# PCB_Punto_de_CobroV2.net
KiCad netlist of a schematic drawn in EAGLE
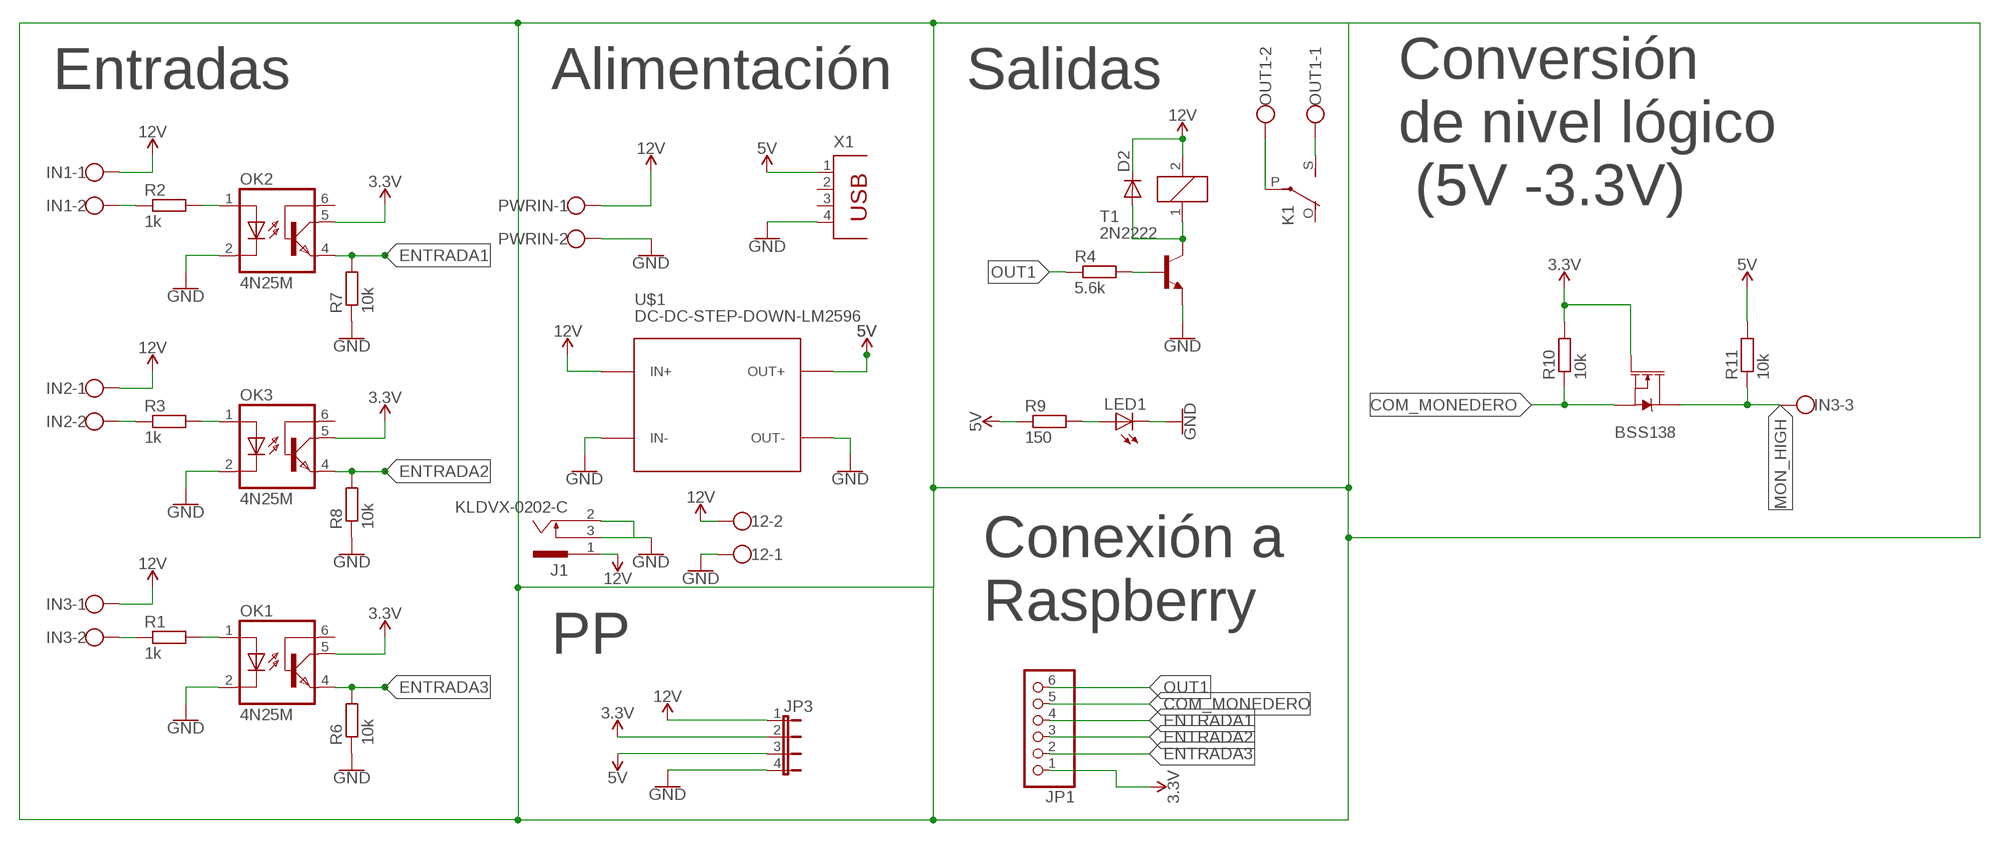
[diagram p0: schematic, sheet 1]

(export (version "E")
  (design (tool "Eeschema 10.0.6"))
  (components
    (comp (ref "12")
      (value "W237-102")
      (footprint "eagle-import:W237-102")
      (fields (field (name "MPN") "237-102"))
      (libsource (lib "eagle-import") (part "W237-102"))
    )
    (comp (ref "D2")
      (value "1N4148DO35-7")
      (footprint "eagle-import:DO35-7")
      (libsource (lib "eagle-import") (part "1N4148DO35-7"))
    )
    (comp (ref "IN1")
      (value "W237-102")
      (footprint "eagle-import:W237-102")
      (fields (field (name "MPN") "237-102"))
      (libsource (lib "eagle-import") (part "W237-102"))
    )
    (comp (ref "IN2")
      (value "W237-102")
      (footprint "eagle-import:W237-102")
      (fields (field (name "MPN") "237-102"))
      (libsource (lib "eagle-import") (part "W237-102"))
    )
    (comp (ref "IN3")
      (value "W237-103")
      (footprint "eagle-import:W237-103")
      (fields (field (name "MPN") "237-103"))
      (libsource (lib "eagle-import") (part "W237-103"))
    )
    (comp (ref "J1")
      (value "KLDVX-0202-C")
      (footprint "eagle-import:KLDVX-0202-C")
      (libsource (lib "eagle-import") (part "KLDVX-0202-C"))
    )
    (comp (ref "JP1")
      (value "PINHD-1X6")
      (footprint "eagle-import:1X06")
      (libsource (lib "eagle-import") (part "PINHD-1X6"))
    )
    (comp (ref "JP3")
      (value "JP4E")
      (footprint "eagle-import:JP4")
      (libsource (lib "eagle-import") (part "JP4E"))
    )
    (comp (ref "K1")
      (value "G5L")
      (footprint "eagle-import:G5LE")
      (libsource (lib "eagle-import") (part "G5L"))
    )
    (comp (ref "LED1")
      (value "LED5MM")
      (footprint "eagle-import:LED5MM")
      (libsource (lib "eagle-import") (part "LED5MM"))
    )
    (comp (ref "OK1")
      (value "4N25M")
      (footprint "eagle-import:DIL06")
      (fields (field (name "MPN") "4N25-M"))
      (libsource (lib "eagle-import") (part "4N?M25"))
    )
    (comp (ref "OK2")
      (value "4N25M")
      (footprint "eagle-import:DIL06")
      (fields (field (name "MPN") "4N25-M"))
      (libsource (lib "eagle-import") (part "4N?M25"))
    )
    (comp (ref "OK3")
      (value "4N25M")
      (footprint "eagle-import:DIL06")
      (fields (field (name "MPN") "4N25-M"))
      (libsource (lib "eagle-import") (part "4N?M25"))
    )
    (comp (ref "OUT1")
      (value "W237-102")
      (footprint "eagle-import:W237-102")
      (fields (field (name "MPN") "237-102"))
      (libsource (lib "eagle-import") (part "W237-102"))
    )
    (comp (ref "PWRIN")
      (value "W237-102")
      (footprint "eagle-import:W237-102")
      (fields (field (name "MPN") "237-102"))
      (libsource (lib "eagle-import") (part "W237-102"))
    )
    (comp (ref "Q3")
      (value "BSS138")
      (footprint "eagle-import:SOT23-3")
      (libsource (lib "eagle-import") (part "MOSFET-NCH-BSS138"))
    )
    (comp (ref "R1")
      (value "1k")
      (footprint "eagle-import:0204_7")
      (libsource (lib "eagle-import") (part "R0204/7"))
    )
    (comp (ref "R2")
      (value "1k")
      (footprint "eagle-import:0204_7")
      (libsource (lib "eagle-import") (part "R0204/7"))
    )
    (comp (ref "R3")
      (value "1k")
      (footprint "eagle-import:0204_7")
      (libsource (lib "eagle-import") (part "R0204/7"))
    )
    (comp (ref "R4")
      (value "5.6k")
      (footprint "eagle-import:0204_7")
      (libsource (lib "eagle-import") (part "R0204/7"))
    )
    (comp (ref "R6")
      (value "10k")
      (footprint "eagle-import:0204_7")
      (libsource (lib "eagle-import") (part "R0204/7"))
    )
    (comp (ref "R7")
      (value "10k")
      (footprint "eagle-import:0204_7")
      (libsource (lib "eagle-import") (part "R0204/7"))
    )
    (comp (ref "R8")
      (value "10k")
      (footprint "eagle-import:0204_7")
      (libsource (lib "eagle-import") (part "R0204/7"))
    )
    (comp (ref "R9")
      (value "150")
      (footprint "eagle-import:0204_7")
      (libsource (lib "eagle-import") (part "R0204/7"))
    )
    (comp (ref "R10")
      (value "10k")
      (footprint "eagle-import:0204_7")
      (libsource (lib "eagle-import") (part "R0204/7"))
    )
    (comp (ref "R11")
      (value "10k")
      (footprint "eagle-import:0204_7")
      (libsource (lib "eagle-import") (part "R0204/7"))
    )
    (comp (ref "T1")
      (value "2N2222")
      (footprint "eagle-import:TO18")
      (libsource (lib "eagle-import") (part "2N2222"))
    )
    (comp (ref "U$1")
      (value "DC-DC-STEP-DOWN-LM2596")
      (footprint "eagle-import:DC-DC-STEP-DOWN-LM2596")
      (libsource (lib "eagle-import") (part "DC-DC-STEP-DOWN-LM2596"))
    )
    (comp (ref "X1")
      (value "PN87520")
      (footprint "eagle-import:PN87520")
      (libsource (lib "eagle-import") (part "PN87520"))
    )
  )
  (nets
    (net (code "1") (name "3.3V") (class "Default")
      (node (ref "JP1") (pin "1") (pinfunction "1_1") (pintype "passive"))
      (node (ref "JP3") (pin "2") (pinfunction "2_2") (pintype "passive"))
      (node (ref "OK1") (pin "5") (pinfunction "COL_5") (pintype "passive"))
      (node (ref "OK2") (pin "5") (pinfunction "COL_5") (pintype "passive"))
      (node (ref "OK3") (pin "5") (pinfunction "COL_5") (pintype "passive"))
      (node (ref "Q3") (pin "1") (pinfunction "G_1") (pintype "bidirectional"))
      (node (ref "R10") (pin "2") (pinfunction "2_2") (pintype "passive"))
    )
    (net (code "2") (name "5V") (class "Default")
      (node (ref "JP3") (pin "3") (pinfunction "3_3") (pintype "passive"))
      (node (ref "R11") (pin "2") (pinfunction "2_2") (pintype "passive"))
      (node (ref "R9") (pin "1") (pinfunction "1_1") (pintype "passive"))
      (node (ref "U$1") (pin "OUT+") (pinfunction "OUT+_OUT+") (pintype "bidirectional"))
      (node (ref "X1") (pin "1") (pinfunction "1_1") (pintype "passive"))
    )
    (net (code "3") (name "12V") (class "Default")
      (node (ref "12") (pin "2") (pinfunction "KL_2") (pintype "passive"))
      (node (ref "D2") (pin "C") (pinfunction "C_C") (pintype "passive"))
      (node (ref "IN1") (pin "1") (pinfunction "KL_1") (pintype "passive"))
      (node (ref "IN2") (pin "1") (pinfunction "KL_1") (pintype "passive"))
      (node (ref "IN3") (pin "1") (pinfunction "KL_1") (pintype "passive"))
      (node (ref "J1") (pin "1") (pinfunction "1_1") (pintype "passive"))
      (node (ref "JP3") (pin "1") (pinfunction "1_1") (pintype "passive"))
      (node (ref "K1") (pin "2") (pinfunction "2_2") (pintype "passive"))
      (node (ref "PWRIN") (pin "1") (pinfunction "KL_1") (pintype "passive"))
      (node (ref "U$1") (pin "IN+") (pinfunction "IN+_IN+") (pintype "bidirectional"))
    )
    (net (code "4") (name "COM_MONEDERO") (class "Default")
      (node (ref "JP1") (pin "5") (pinfunction "5_5") (pintype "passive"))
      (node (ref "Q3") (pin "2") (pinfunction "S_2") (pintype "bidirectional"))
      (node (ref "R10") (pin "1") (pinfunction "1_1") (pintype "passive"))
    )
    (net (code "5") (name "ENTRADA1") (class "Default")
      (node (ref "JP1") (pin "4") (pinfunction "4_4") (pintype "passive"))
      (node (ref "OK2") (pin "4") (pinfunction "EMI_4") (pintype "passive"))
      (node (ref "R7") (pin "2") (pinfunction "2_2") (pintype "passive"))
    )
    (net (code "6") (name "ENTRADA2") (class "Default")
      (node (ref "JP1") (pin "3") (pinfunction "3_3") (pintype "passive"))
      (node (ref "OK3") (pin "4") (pinfunction "EMI_4") (pintype "passive"))
      (node (ref "R8") (pin "2") (pinfunction "2_2") (pintype "passive"))
    )
    (net (code "7") (name "ENTRADA3") (class "Default")
      (node (ref "JP1") (pin "2") (pinfunction "2_2") (pintype "passive"))
      (node (ref "OK1") (pin "4") (pinfunction "EMI_4") (pintype "passive"))
      (node (ref "R6") (pin "2") (pinfunction "2_2") (pintype "passive"))
    )
    (net (code "8") (name "GND") (class "Default")
      (node (ref "12") (pin "1") (pinfunction "KL_1") (pintype "passive"))
      (node (ref "J1") (pin "2") (pinfunction "2_2") (pintype "passive"))
      (node (ref "J1") (pin "3") (pinfunction "3_3") (pintype "passive"))
      (node (ref "JP3") (pin "4") (pinfunction "4_4") (pintype "passive"))
      (node (ref "LED1") (pin "K") (pinfunction "C_K") (pintype "passive"))
      (node (ref "OK1") (pin "2") (pinfunction "C_2") (pintype "passive"))
      (node (ref "OK2") (pin "2") (pinfunction "C_2") (pintype "passive"))
      (node (ref "OK3") (pin "2") (pinfunction "C_2") (pintype "passive"))
      (node (ref "PWRIN") (pin "2") (pinfunction "KL_2") (pintype "passive"))
      (node (ref "R6") (pin "1") (pinfunction "1_1") (pintype "passive"))
      (node (ref "R7") (pin "1") (pinfunction "1_1") (pintype "passive"))
      (node (ref "R8") (pin "1") (pinfunction "1_1") (pintype "passive"))
      (node (ref "T1") (pin "1") (pinfunction "E_1") (pintype "passive"))
      (node (ref "U$1") (pin "IN-") (pinfunction "IN-_IN-") (pintype "bidirectional"))
      (node (ref "U$1") (pin "OUT-") (pinfunction "OUT-_OUT-") (pintype "bidirectional"))
      (node (ref "X1") (pin "4") (pinfunction "4_4") (pintype "passive"))
    )
    (net (code "9") (name "MON_HIGH") (class "Default")
      (node (ref "IN3") (pin "3") (pinfunction "KL_3") (pintype "passive"))
      (node (ref "Q3") (pin "3") (pinfunction "D_3") (pintype "bidirectional"))
      (node (ref "R11") (pin "1") (pinfunction "1_1") (pintype "passive"))
    )
    (net (code "10") (name "Net-(IN1B-KL)") (class "Default")
      (node (ref "IN1") (pin "2") (pinfunction "KL_2") (pintype "passive"))
      (node (ref "R2") (pin "1") (pinfunction "1_1") (pintype "passive"))
    )
    (net (code "11") (name "Net-(IN2B-KL)") (class "Default")
      (node (ref "IN2") (pin "2") (pinfunction "KL_2") (pintype "passive"))
      (node (ref "R3") (pin "1") (pinfunction "1_1") (pintype "passive"))
    )
    (net (code "12") (name "Net-(IN3B-KL)") (class "Default")
      (node (ref "IN3") (pin "2") (pinfunction "KL_2") (pintype "passive"))
      (node (ref "R1") (pin "1") (pinfunction "1_1") (pintype "passive"))
    )
    (net (code "13") (name "Net-(LED1-PadA)") (class "Default")
      (node (ref "LED1") (pin "A") (pinfunction "A_A") (pintype "passive"))
      (node (ref "R9") (pin "2") (pinfunction "2_2") (pintype "passive"))
    )
    (net (code "14") (name "Net-(OK1-A)") (class "Default")
      (node (ref "OK1") (pin "1") (pinfunction "A_1") (pintype "passive"))
      (node (ref "R1") (pin "2") (pinfunction "2_2") (pintype "passive"))
    )
    (net (code "15") (name "Net-(OK2-A)") (class "Default")
      (node (ref "OK2") (pin "1") (pinfunction "A_1") (pintype "passive"))
      (node (ref "R2") (pin "2") (pinfunction "2_2") (pintype "passive"))
    )
    (net (code "16") (name "Net-(OK3-A)") (class "Default")
      (node (ref "OK3") (pin "1") (pinfunction "A_1") (pintype "passive"))
      (node (ref "R3") (pin "2") (pinfunction "2_2") (pintype "passive"))
    )
    (net (code "17") (name "Net-(OUT1A-KL)") (class "Default")
      (node (ref "K1") (pin "S") (pinfunction "S_S") (pintype "passive"))
      (node (ref "OUT1") (pin "1") (pinfunction "KL_1") (pintype "passive"))
    )
    (net (code "18") (name "Net-(OUT1B-KL)") (class "Default")
      (node (ref "K1") (pin "P") (pinfunction "P_P") (pintype "passive"))
      (node (ref "OUT1") (pin "2") (pinfunction "KL_2") (pintype "passive"))
    )
    (net (code "19") (name "Net-(T1-B)") (class "Default")
      (node (ref "R4") (pin "2") (pinfunction "2_2") (pintype "passive"))
      (node (ref "T1") (pin "2") (pinfunction "B_2") (pintype "passive"))
    )
    (net (code "20") (name "Net-(T1-C)") (class "Default")
      (node (ref "D2") (pin "A") (pinfunction "A_A") (pintype "passive"))
      (node (ref "K1") (pin "1") (pinfunction "1_1") (pintype "passive"))
      (node (ref "T1") (pin "3") (pinfunction "C_3") (pintype "passive"))
    )
    (net (code "21") (name "OUT1") (class "Default")
      (node (ref "JP1") (pin "6") (pinfunction "6_6") (pintype "passive"))
      (node (ref "R4") (pin "1") (pinfunction "1_1") (pintype "passive"))
    )
    (net (code "22") (name "unconnected-(J1-1-Pad1@1)") (class "Default")
      (node (ref "J1") (pin "1@1") (pinfunction "1_1@1") (pintype "passive"))
    )
    (net (code "23") (name "unconnected-(J1-2-Pad2@1)") (class "Default")
      (node (ref "J1") (pin "2@1") (pinfunction "2_2@1") (pintype "passive"))
    )
    (net (code "24") (name "unconnected-(J1-3-Pad3@1)") (class "Default")
      (node (ref "J1") (pin "3@1") (pinfunction "3_3@1") (pintype "passive"))
    )
    (net (code "25") (name "unconnected-(K1-PadO)") (class "Default")
      (node (ref "K1") (pin "O") (pinfunction "O_O") (pintype "passive"))
    )
    (net (code "26") (name "unconnected-(OK1-BAS-Pad6)") (class "Default")
      (node (ref "OK1") (pin "6") (pinfunction "BAS_6") (pintype "passive"))
    )
    (net (code "27") (name "unconnected-(OK2-BAS-Pad6)") (class "Default")
      (node (ref "OK2") (pin "6") (pinfunction "BAS_6") (pintype "passive"))
    )
    (net (code "28") (name "unconnected-(OK3-BAS-Pad6)") (class "Default")
      (node (ref "OK3") (pin "6") (pinfunction "BAS_6") (pintype "passive"))
    )
    (net (code "29") (name "unconnected-(X1-Pad2)") (class "Default")
      (node (ref "X1") (pin "2") (pinfunction "2_2") (pintype "passive"))
    )
    (net (code "30") (name "unconnected-(X1-Pad3)") (class "Default")
      (node (ref "X1") (pin "3") (pinfunction "3_3") (pintype "passive"))
    )
  )
)
